# LDO.net
KiCad netlist of a schematic drawn in Altium Designer
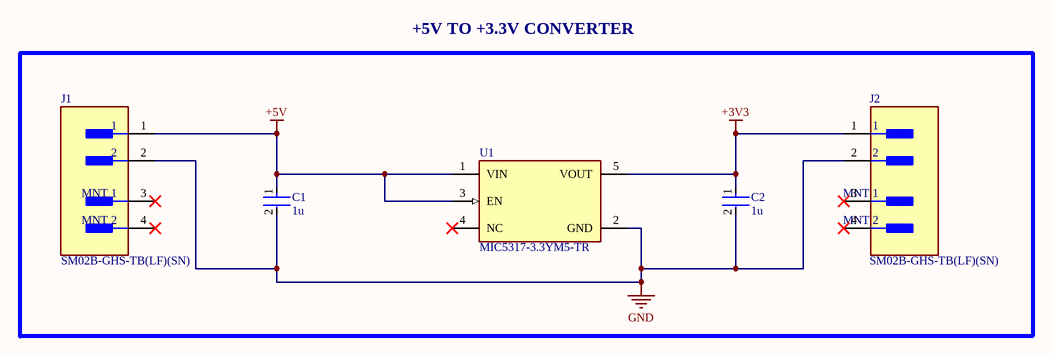
[diagram p0: LDO.SchDoc]

(export (version "E")
  (design (tool "Eeschema 10.0.6"))
  (components
    (comp (ref "C1")
      (value "1u")
      (footprint "FP-CC0805-0_85-MFG")
      (description "CAP CER 1UF 10V X7R 0805")
      (fields
        (field (name "MANUFACTURER") "Yageo")
        (field (name "OCTOPART") "https://octopart.com/cc0805kkx7r6bb105-yageo-42522859")
      )
      (libsource (lib "Altium Content Vault") (part "11868f565c42a9108669ba33697ecf6"))
    )
    (comp (ref "C2")
      (value "1u")
      (footprint "FP-CC0805-0_85-MFG")
      (description "CAP CER 1UF 10V X7R 0805")
      (fields
        (field (name "MANUFACTURER") "Yageo")
        (field (name "OCTOPART") "https://octopart.com/cc0805kkx7r6bb105-yageo-42522859")
      )
      (libsource (lib "Altium Content Vault") (part "11868f565c42a9108669ba33697ecf6"))
    )
    (comp (ref "J1")
      (value "SM02B-GHS-TB(LF)(SN)")
      (footprint "FP-SM02B-GHS-TB_LF_SN-MFG")
      (description "CONN HEADER SMD R/A 2POS 1.25MM")
      (libsource (lib "") (part "56ec3178a87b3978bdc1b3682cd516a_1"))
    )
    (comp (ref "J2")
      (value "SM02B-GHS-TB(LF)(SN)")
      (footprint "FP-SM02B-GHS-TB_LF_SN-MFG")
      (description "CONN HEADER SMD R/A 2POS 1.25MM")
      (libsource (lib "Altium Content Vault") (part "56ec3178a87b3978bdc1b3682cd516a"))
    )
    (comp (ref "U1")
      (value "MIC5317-3.3YM5-TR")
      (footprint "FP-SOT23-5LD-PL-1-MFG")
      (description "IC REG LINEAR 3.3V 150MA SOT23-5")
      (libsource (lib "Altium Content Vault") (part "0a093dae7315cdc977fd108dde87457"))
    )
  )
  (nets
    (net (code "1") (name "+3V3") (class "Default")
      (node (ref "C2") (pin "1") (pinfunction "1_1") (pintype "passive"))
      (node (ref "J2") (pin "1") (pinfunction "1_1") (pintype "passive"))
      (node (ref "U1") (pin "5") (pinfunction "VOUT_5") (pintype "power_in"))
    )
    (net (code "2") (name "+5V") (class "Default")
      (node (ref "C1") (pin "1") (pinfunction "1_1") (pintype "passive"))
      (node (ref "J1") (pin "1") (pinfunction "1_1") (pintype "passive"))
      (node (ref "U1") (pin "1") (pinfunction "VIN_1") (pintype "power_in"))
      (node (ref "U1") (pin "3") (pinfunction "EN_3") (pintype "input"))
    )
    (net (code "3") (name "GND") (class "Default")
      (node (ref "C1") (pin "2") (pinfunction "2_2") (pintype "passive"))
      (node (ref "C2") (pin "2") (pinfunction "2_2") (pintype "passive"))
      (node (ref "J1") (pin "2") (pinfunction "2_2") (pintype "passive"))
      (node (ref "J2") (pin "2") (pinfunction "2_2") (pintype "passive"))
      (node (ref "U1") (pin "2") (pinfunction "GND_2") (pintype "power_in"))
    )
    (net (code "4") (name "unconnected-(J1-MNT_1-Pad3)") (class "Default")
      (node (ref "J1") (pin "3") (pinfunction "MNT_1_3") (pintype "passive+no_connect"))
    )
    (net (code "5") (name "unconnected-(J1-MNT_2-Pad4)") (class "Default")
      (node (ref "J1") (pin "4") (pinfunction "MNT_2_4") (pintype "passive+no_connect"))
    )
    (net (code "6") (name "unconnected-(J2-MNT_1-Pad3)") (class "Default")
      (node (ref "J2") (pin "3") (pinfunction "MNT_1_3") (pintype "passive+no_connect"))
    )
    (net (code "7") (name "unconnected-(J2-MNT_2-Pad4)") (class "Default")
      (node (ref "J2") (pin "4") (pinfunction "MNT_2_4") (pintype "passive+no_connect"))
    )
    (net (code "8") (name "unconnected-(U1-NC-Pad4)") (class "Default")
      (node (ref "U1") (pin "4") (pinfunction "NC_4") (pintype "passive+no_connect"))
    )
  )
)
